# 3_RKSTM32_Peripheral.net
KiCad netlist of a schematic drawn in Altium Designer
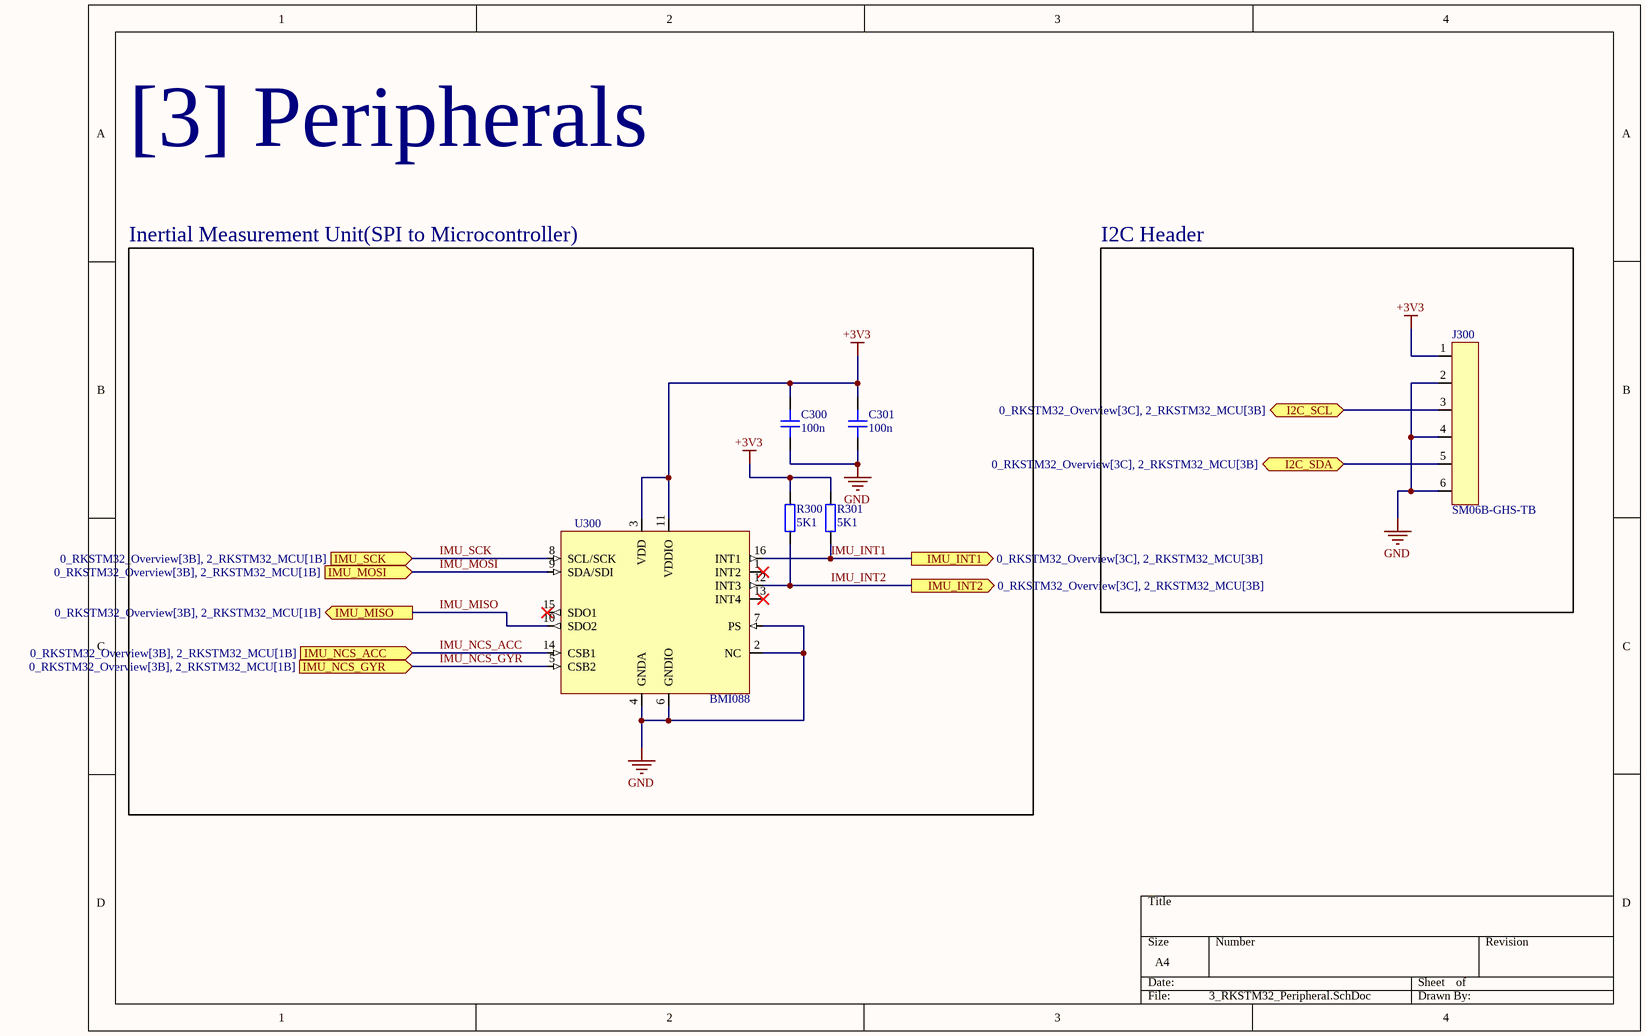
[diagram p0: 3_RKSTM32_Peripheral.SchDoc]

(export (version "E")
  (design (tool "Eeschema 10.0.6"))
  (components
    (comp (ref "C300")
      (value "100n")
      (footprint "CAP_0805")
      (description "Capacitor SMD 0805")
      (libsource (lib "Schematic-Lib-PhilsLab") (part "CAP_0805"))
    )
    (comp (ref "C301")
      (value "100n")
      (footprint "CAP_0805")
      (description "Capacitor SMD 0805")
      (libsource (lib "Schematic-Lib-PhilsLab") (part "CAP_0805"))
    )
    (comp (ref "J300")
      (value "SM06B-GHS-TB")
      (footprint "SM06B-GHS-TB")
      (description "Header Connector 6 Position 1.25MM Pitch SMD Horizontal JST GH")
      (fields (field (name "MANUFACTURER") "JST"))
      (libsource (lib "Schematic-Lib-PhilsLab") (part "SM06B-GHS-TB"))
    )
    (comp (ref "R300")
      (value "5K1")
      (footprint "RES_0603")
      (description "Resistor SMD 0603")
      (libsource (lib "Schematic-Lib-PhilsLab") (part "RES_0603"))
    )
    (comp (ref "R301")
      (value "5K1")
      (footprint "RES_0603")
      (description "Resistor SMD 0603")
      (libsource (lib "Schematic-Lib-PhilsLab") (part "RES_0603"))
    )
    (comp (ref "U300")
      (value "BMI088")
      (footprint "BMI088")
      (description "Inertial Measurement Unit IMU 6-Axis LGA")
      (fields (field (name "MANUFACTURER") "Bosch"))
      (libsource (lib "Schematic-Lib-PhilsLab") (part "BMI088"))
    )
  )
  (nets
    (net (code "1") (name "+3V3") (class "Default")
      (node (ref "C300") (pin "2") (pinfunction "2_2") (pintype "passive"))
      (node (ref "C301") (pin "2") (pinfunction "2_2") (pintype "passive"))
      (node (ref "J300") (pin "1") (pinfunction "1_1") (pintype "passive"))
      (node (ref "R300") (pin "2") (pinfunction "2_2") (pintype "passive"))
      (node (ref "R301") (pin "2") (pinfunction "2_2") (pintype "passive"))
      (node (ref "U300") (pin "11") (pinfunction "VDDIO_11") (pintype "power_in"))
      (node (ref "U300") (pin "3") (pinfunction "VDD_3") (pintype "power_in"))
    )
    (net (code "2") (name "/I2C_SCL") (class "Default")
      (node (ref "J300") (pin "3") (pinfunction "3_3") (pintype "passive"))
    )
    (net (code "3") (name "/I2C_SDA") (class "Default")
      (node (ref "J300") (pin "5") (pinfunction "5_5") (pintype "passive"))
    )
    (net (code "4") (name "/IMU_INT1") (class "Default")
      (node (ref "R301") (pin "1") (pinfunction "1_1") (pintype "passive"))
      (node (ref "U300") (pin "16") (pinfunction "INT1_16") (pintype "output"))
    )
    (net (code "5") (name "/IMU_INT2") (class "Default")
      (node (ref "R300") (pin "1") (pinfunction "1_1") (pintype "passive"))
      (node (ref "U300") (pin "12") (pinfunction "INT3_12") (pintype "output"))
    )
    (net (code "6") (name "/IMU_MISO") (class "Default")
      (node (ref "U300") (pin "10") (pinfunction "SDO2_10") (pintype "output"))
    )
    (net (code "7") (name "/IMU_MOSI") (class "Default")
      (node (ref "U300") (pin "9") (pinfunction "SDA/SDI_9") (pintype "input"))
    )
    (net (code "8") (name "/IMU_NCS_ACC") (class "Default")
      (node (ref "U300") (pin "14") (pinfunction "CSB1_14") (pintype "input"))
    )
    (net (code "9") (name "/IMU_NCS_GYR") (class "Default")
      (node (ref "U300") (pin "5") (pinfunction "CSB2_5") (pintype "input"))
    )
    (net (code "10") (name "/IMU_SCK") (class "Default")
      (node (ref "U300") (pin "8") (pinfunction "SCL/SCK_8") (pintype "input"))
    )
    (net (code "11") (name "GND") (class "Default")
      (node (ref "C300") (pin "1") (pinfunction "1_1") (pintype "passive"))
      (node (ref "C301") (pin "1") (pinfunction "1_1") (pintype "passive"))
      (node (ref "J300") (pin "2") (pinfunction "2_2") (pintype "passive"))
      (node (ref "J300") (pin "4") (pinfunction "4_4") (pintype "passive"))
      (node (ref "J300") (pin "6") (pinfunction "6_6") (pintype "passive"))
      (node (ref "U300") (pin "2") (pinfunction "NC_2") (pintype "passive"))
      (node (ref "U300") (pin "4") (pinfunction "GNDA_4") (pintype "power_in"))
      (node (ref "U300") (pin "6") (pinfunction "GNDIO_6") (pintype "power_in"))
      (node (ref "U300") (pin "7") (pinfunction "PS_7") (pintype "input"))
    )
    (net (code "12") (name "unconnected-(U300-INT2-Pad1)") (class "Default")
      (node (ref "U300") (pin "1") (pinfunction "INT2_1") (pintype "bidirectional+no_connect"))
    )
    (net (code "13") (name "unconnected-(U300-INT4-Pad13)") (class "Default")
      (node (ref "U300") (pin "13") (pinfunction "INT4_13") (pintype "bidirectional+no_connect"))
    )
    (net (code "14") (name "unconnected-(U300-SDO1-Pad15)") (class "Default")
      (node (ref "U300") (pin "15") (pinfunction "SDO1_15") (pintype "output+no_connect"))
    )
  )
)
